# r2r.net
KiCad netlist of a schematic drawn in EAGLE
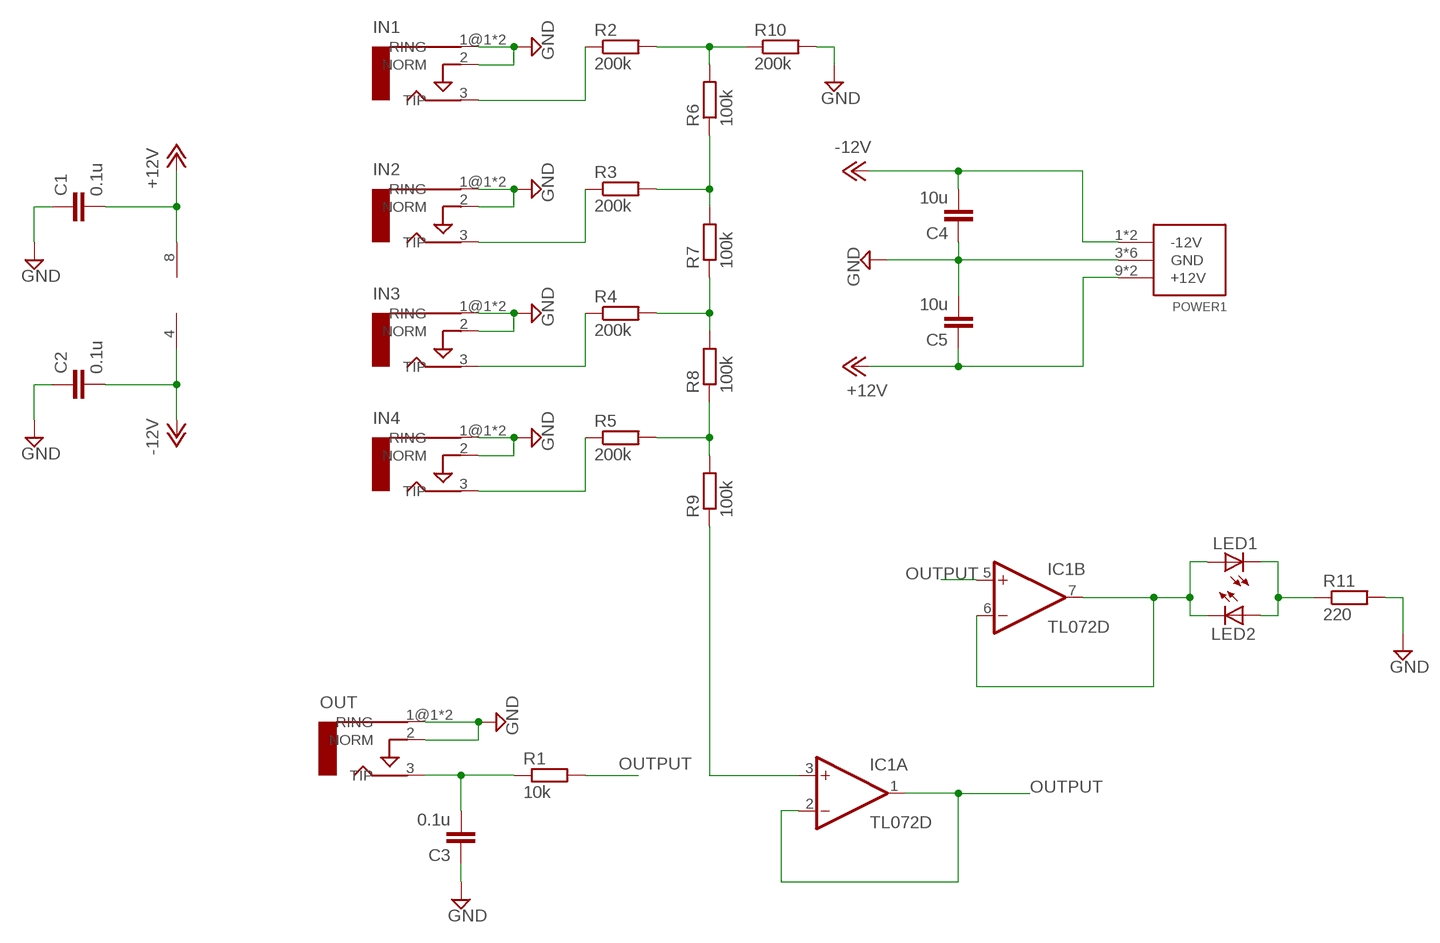
[diagram p0: schematic, sheet 1]

(export (version "E")
  (design (tool "Eeschema 10.0.6"))
  (components
    (comp (ref "C1")
      (value "0.1u")
      (footprint "eagle-import:C0805")
      (libsource (lib "eagle-import") (part "C-EUC0805"))
    )
    (comp (ref "C2")
      (value "0.1u")
      (footprint "eagle-import:C0805")
      (libsource (lib "eagle-import") (part "C-EUC0805"))
    )
    (comp (ref "C3")
      (value "0.1u")
      (footprint "eagle-import:C0805")
      (libsource (lib "eagle-import") (part "C-EUC0805"))
    )
    (comp (ref "C4")
      (value "10u")
      (footprint "eagle-import:C0805")
      (libsource (lib "eagle-import") (part "C-EUC0805"))
    )
    (comp (ref "C5")
      (value "10u")
      (footprint "eagle-import:C0805")
      (libsource (lib "eagle-import") (part "C-EUC0805"))
    )
    (comp (ref "IC1")
      (value "TL072D")
      (footprint "eagle-import:SO08")
      (libsource (lib "eagle-import") (part "TL072D"))
    )
    (comp (ref "IN1")
      (value "AUDIO-JACKERTHENVAR")
      (footprint "eagle-import:ERTHENVAR-JACK")
      (libsource (lib "eagle-import") (part "AUDIO-JACKERTHENVAR"))
    )
    (comp (ref "IN2")
      (value "AUDIO-JACKERTHENVAR")
      (footprint "eagle-import:ERTHENVAR-JACK")
      (libsource (lib "eagle-import") (part "AUDIO-JACKERTHENVAR"))
    )
    (comp (ref "IN3")
      (value "AUDIO-JACKERTHENVAR")
      (footprint "eagle-import:ERTHENVAR-JACK")
      (libsource (lib "eagle-import") (part "AUDIO-JACKERTHENVAR"))
    )
    (comp (ref "IN4")
      (value "AUDIO-JACKERTHENVAR")
      (footprint "eagle-import:ERTHENVAR-JACK")
      (libsource (lib "eagle-import") (part "AUDIO-JACKERTHENVAR"))
    )
    (comp (ref "LED1")
      (value "LEDCHIP-LED0805")
      (footprint "eagle-import:CHIP-LED0805")
      (libsource (lib "eagle-import") (part "LEDCHIP-LED0805"))
    )
    (comp (ref "LED2")
      (value "LEDCHIP-LED0805")
      (footprint "eagle-import:CHIP-LED0805")
      (libsource (lib "eagle-import") (part "LEDCHIP-LED0805"))
    )
    (comp (ref "OUT")
      (value "AUDIO-JACKERTHENVAR")
      (footprint "eagle-import:ERTHENVAR-JACK")
      (libsource (lib "eagle-import") (part "AUDIO-JACKERTHENVAR"))
    )
    (comp (ref "POWER1")
      (value "POWER_SIMPLE10")
      (footprint "eagle-import:POWER_10")
      (libsource (lib "eagle-import") (part "POWER_SIMPLE10"))
    )
    (comp (ref "R1")
      (value "10k")
      (footprint "eagle-import:R0805")
      (libsource (lib "eagle-import") (part "R-EU_R0805"))
    )
    (comp (ref "R2")
      (value "200k")
      (footprint "eagle-import:R0805")
      (libsource (lib "eagle-import") (part "R-EU_R0805"))
    )
    (comp (ref "R3")
      (value "200k")
      (footprint "eagle-import:R0805")
      (libsource (lib "eagle-import") (part "R-EU_R0805"))
    )
    (comp (ref "R4")
      (value "200k")
      (footprint "eagle-import:R0805")
      (libsource (lib "eagle-import") (part "R-EU_R0805"))
    )
    (comp (ref "R5")
      (value "200k")
      (footprint "eagle-import:R0805")
      (libsource (lib "eagle-import") (part "R-EU_R0805"))
    )
    (comp (ref "R6")
      (value "100k")
      (footprint "eagle-import:R0805")
      (libsource (lib "eagle-import") (part "R-EU_R0805"))
    )
    (comp (ref "R7")
      (value "100k")
      (footprint "eagle-import:R0805")
      (libsource (lib "eagle-import") (part "R-EU_R0805"))
    )
    (comp (ref "R8")
      (value "100k")
      (footprint "eagle-import:R0805")
      (libsource (lib "eagle-import") (part "R-EU_R0805"))
    )
    (comp (ref "R9")
      (value "100k")
      (footprint "eagle-import:R0805")
      (libsource (lib "eagle-import") (part "R-EU_R0805"))
    )
    (comp (ref "R10")
      (value "200k")
      (footprint "eagle-import:R0805")
      (libsource (lib "eagle-import") (part "R-EU_R0805"))
    )
    (comp (ref "R11")
      (value "220")
      (footprint "eagle-import:R0805")
      (libsource (lib "eagle-import") (part "R-EU_R0805"))
    )
  )
  (nets
    (net (code "1") (name "+12V") (class "Default")
      (node (ref "C1") (pin "2") (pinfunction "2_2") (pintype "passive"))
      (node (ref "C5") (pin "1") (pinfunction "1_1") (pintype "passive"))
      (node (ref "IC1") (pin "8") (pinfunction "V+_8") (pintype "power_in"))
      (node (ref "POWER1") (pin "10") (pinfunction "+12V_10") (pintype "bidirectional"))
      (node (ref "POWER1") (pin "9") (pinfunction "+12V_9") (pintype "bidirectional"))
    )
    (net (code "2") (name "-12V") (class "Default")
      (node (ref "C2") (pin "2") (pinfunction "2_2") (pintype "passive"))
      (node (ref "C4") (pin "2") (pinfunction "2_2") (pintype "passive"))
      (node (ref "IC1") (pin "4") (pinfunction "V-_4") (pintype "power_in"))
      (node (ref "POWER1") (pin "1") (pinfunction "-12V_1") (pintype "bidirectional"))
      (node (ref "POWER1") (pin "2") (pinfunction "-12V_2") (pintype "bidirectional"))
    )
    (net (code "3") (name "/OUTPUT") (class "Default")
      (node (ref "IC1") (pin "1") (pinfunction "OUT_1") (pintype "output"))
      (node (ref "IC1") (pin "2") (pinfunction "-IN_2") (pintype "input"))
      (node (ref "IC1") (pin "5") (pinfunction "+IN_5") (pintype "input"))
      (node (ref "R1") (pin "2") (pinfunction "2_2") (pintype "passive"))
    )
    (net (code "4") (name "GND") (class "Default")
      (node (ref "C1") (pin "1") (pinfunction "1_1") (pintype "passive"))
      (node (ref "C2") (pin "1") (pinfunction "1_1") (pintype "passive"))
      (node (ref "C3") (pin "1") (pinfunction "1_1") (pintype "passive"))
      (node (ref "C4") (pin "1") (pinfunction "1_1") (pintype "passive"))
      (node (ref "C5") (pin "2") (pinfunction "2_2") (pintype "passive"))
      (node (ref "IN1") (pin "1@1") (pinfunction "RING_1@1") (pintype "bidirectional"))
      (node (ref "IN1") (pin "1@2") (pinfunction "RING_1@2") (pintype "bidirectional"))
      (node (ref "IN1") (pin "2") (pinfunction "NORM_2") (pintype "bidirectional"))
      (node (ref "IN2") (pin "1@1") (pinfunction "RING_1@1") (pintype "bidirectional"))
      (node (ref "IN2") (pin "1@2") (pinfunction "RING_1@2") (pintype "bidirectional"))
      (node (ref "IN2") (pin "2") (pinfunction "NORM_2") (pintype "bidirectional"))
      (node (ref "IN3") (pin "1@1") (pinfunction "RING_1@1") (pintype "bidirectional"))
      (node (ref "IN3") (pin "1@2") (pinfunction "RING_1@2") (pintype "bidirectional"))
      (node (ref "IN3") (pin "2") (pinfunction "NORM_2") (pintype "bidirectional"))
      (node (ref "IN4") (pin "1@1") (pinfunction "RING_1@1") (pintype "bidirectional"))
      (node (ref "IN4") (pin "1@2") (pinfunction "RING_1@2") (pintype "bidirectional"))
      (node (ref "IN4") (pin "2") (pinfunction "NORM_2") (pintype "bidirectional"))
      (node (ref "OUT") (pin "1@1") (pinfunction "RING_1@1") (pintype "bidirectional"))
      (node (ref "OUT") (pin "1@2") (pinfunction "RING_1@2") (pintype "bidirectional"))
      (node (ref "OUT") (pin "2") (pinfunction "NORM_2") (pintype "bidirectional"))
      (node (ref "POWER1") (pin "3") (pinfunction "GND_3") (pintype "bidirectional"))
      (node (ref "POWER1") (pin "4") (pinfunction "GND_4") (pintype "bidirectional"))
      (node (ref "POWER1") (pin "5") (pinfunction "GND_5") (pintype "bidirectional"))
      (node (ref "POWER1") (pin "6") (pinfunction "GND_6") (pintype "bidirectional"))
      (node (ref "POWER1") (pin "7") (pinfunction "GND_7") (pintype "bidirectional"))
      (node (ref "POWER1") (pin "8") (pinfunction "GND_8") (pintype "bidirectional"))
      (node (ref "R10") (pin "2") (pinfunction "2_2") (pintype "passive"))
      (node (ref "R11") (pin "2") (pinfunction "2_2") (pintype "passive"))
    )
    (net (code "5") (name "Net-(IC1A-+IN)") (class "Default")
      (node (ref "IC1") (pin "3") (pinfunction "+IN_3") (pintype "input"))
      (node (ref "R9") (pin "1") (pinfunction "1_1") (pintype "passive"))
    )
    (net (code "6") (name "Net-(IC1B--IN)") (class "Default")
      (node (ref "IC1") (pin "6") (pinfunction "-IN_6") (pintype "input"))
      (node (ref "IC1") (pin "7") (pinfunction "OUT_7") (pintype "output"))
      (node (ref "LED1") (pin "A") (pinfunction "A_A") (pintype "passive"))
      (node (ref "LED2") (pin "C") (pinfunction "C_C") (pintype "passive"))
    )
    (net (code "7") (name "Net-(IN1-TIP)") (class "Default")
      (node (ref "IN1") (pin "3") (pinfunction "TIP_3") (pintype "bidirectional"))
      (node (ref "R2") (pin "1") (pinfunction "1_1") (pintype "passive"))
    )
    (net (code "8") (name "Net-(IN2-TIP)") (class "Default")
      (node (ref "IN2") (pin "3") (pinfunction "TIP_3") (pintype "bidirectional"))
      (node (ref "R3") (pin "1") (pinfunction "1_1") (pintype "passive"))
    )
    (net (code "9") (name "Net-(IN3-TIP)") (class "Default")
      (node (ref "IN3") (pin "3") (pinfunction "TIP_3") (pintype "bidirectional"))
      (node (ref "R4") (pin "1") (pinfunction "1_1") (pintype "passive"))
    )
    (net (code "10") (name "Net-(IN4-TIP)") (class "Default")
      (node (ref "IN4") (pin "3") (pinfunction "TIP_3") (pintype "bidirectional"))
      (node (ref "R5") (pin "1") (pinfunction "1_1") (pintype "passive"))
    )
    (net (code "11") (name "Net-(LED1-PadC)") (class "Default")
      (node (ref "LED1") (pin "C") (pinfunction "C_C") (pintype "passive"))
      (node (ref "LED2") (pin "A") (pinfunction "A_A") (pintype "passive"))
      (node (ref "R11") (pin "1") (pinfunction "1_1") (pintype "passive"))
    )
    (net (code "12") (name "Net-(OUT-TIP)") (class "Default")
      (node (ref "C3") (pin "2") (pinfunction "2_2") (pintype "passive"))
      (node (ref "OUT") (pin "3") (pinfunction "TIP_3") (pintype "bidirectional"))
      (node (ref "R1") (pin "1") (pinfunction "1_1") (pintype "passive"))
    )
    (net (code "13") (name "Net-(R3-Pad2)") (class "Default")
      (node (ref "R3") (pin "2") (pinfunction "2_2") (pintype "passive"))
      (node (ref "R6") (pin "1") (pinfunction "1_1") (pintype "passive"))
      (node (ref "R7") (pin "2") (pinfunction "2_2") (pintype "passive"))
    )
    (net (code "14") (name "Net-(R4-Pad2)") (class "Default")
      (node (ref "R4") (pin "2") (pinfunction "2_2") (pintype "passive"))
      (node (ref "R7") (pin "1") (pinfunction "1_1") (pintype "passive"))
      (node (ref "R8") (pin "2") (pinfunction "2_2") (pintype "passive"))
    )
    (net (code "15") (name "Net-(R5-Pad2)") (class "Default")
      (node (ref "R5") (pin "2") (pinfunction "2_2") (pintype "passive"))
      (node (ref "R8") (pin "1") (pinfunction "1_1") (pintype "passive"))
      (node (ref "R9") (pin "2") (pinfunction "2_2") (pintype "passive"))
    )
    (net (code "16") (name "Net-(R10-Pad1)") (class "Default")
      (node (ref "R10") (pin "1") (pinfunction "1_1") (pintype "passive"))
      (node (ref "R2") (pin "2") (pinfunction "2_2") (pintype "passive"))
      (node (ref "R6") (pin "2") (pinfunction "2_2") (pintype "passive"))
    )
  )
)
